# LEDs.net
KiCad netlist of a schematic drawn in Altium Designer
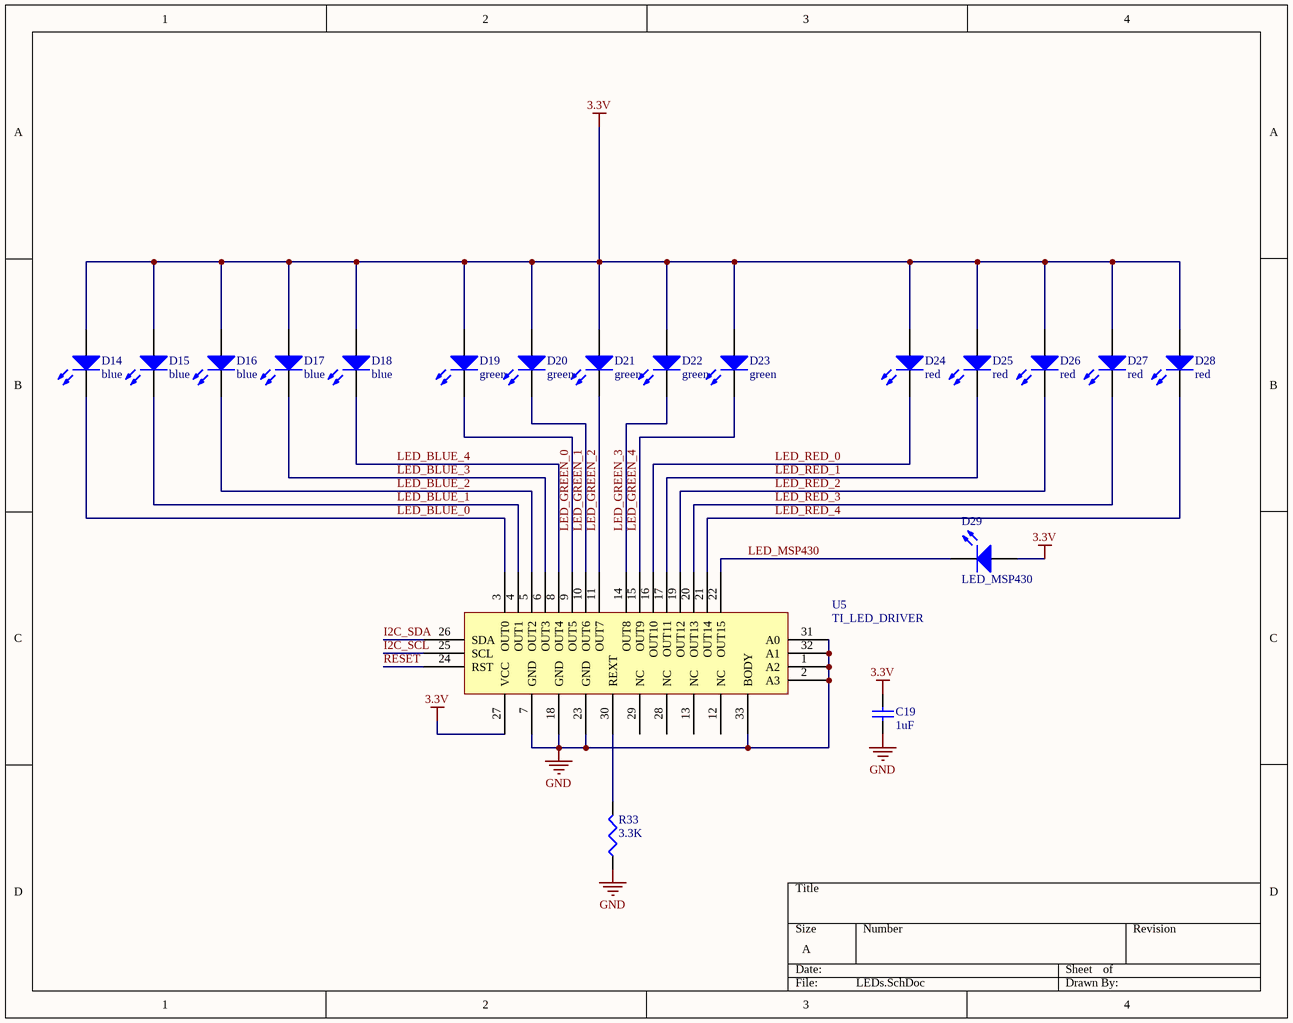
[diagram p0: LEDs.SchDoc]

(export (version "E")
  (design (tool "Eeschema 10.0.6"))
  (components
    (comp (ref "C19")
      (value "1uF")
      (footprint "CAPC1608L")
      (description "Capacitor (Semiconductor SIM Model)")
      (fields (field (name "Comment") "Cap Semi") (field (name "PUBLISHER") "Altium Limited"))
      (libsource (lib "Miscellaneous Devices") (part "Cap Semi"))
    )
    (comp (ref "D14") (value "blue") (footprint "SurfaceMount(603)") (libsource (lib "mrone") (part "LED")))
    (comp (ref "D15") (value "blue") (footprint "SurfaceMount(603)") (libsource (lib "mrone") (part "LED")))
    (comp (ref "D16") (value "blue") (footprint "SurfaceMount(603)") (libsource (lib "mrone") (part "LED")))
    (comp (ref "D17") (value "blue") (footprint "SurfaceMount(603)") (libsource (lib "mrone") (part "LED")))
    (comp (ref "D18") (value "blue") (footprint "SurfaceMount(603)") (libsource (lib "mrone") (part "LED")))
    (comp (ref "D19") (value "green") (footprint "SurfaceMount(603)") (libsource (lib "mrone") (part "LED")))
    (comp (ref "D20") (value "green") (footprint "SurfaceMount(603)") (libsource (lib "mrone") (part "LED")))
    (comp (ref "D21") (value "green") (footprint "SurfaceMount(603)") (libsource (lib "mrone") (part "LED")))
    (comp (ref "D22") (value "green") (footprint "SurfaceMount(603)") (libsource (lib "mrone") (part "LED")))
    (comp (ref "D23") (value "green") (footprint "SurfaceMount(603)") (libsource (lib "mrone") (part "LED")))
    (comp (ref "D24") (value "red") (footprint "SurfaceMount(603)") (libsource (lib "mrone") (part "LED")))
    (comp (ref "D25") (value "red") (footprint "SurfaceMount(603)") (libsource (lib "mrone") (part "LED")))
    (comp (ref "D26") (value "red") (footprint "SurfaceMount(603)") (libsource (lib "mrone") (part "LED")))
    (comp (ref "D27") (value "red") (footprint "SurfaceMount(603)") (libsource (lib "mrone") (part "LED")))
    (comp (ref "D28") (value "red") (footprint "SurfaceMount(603)") (libsource (lib "mrone") (part "LED")))
    (comp (ref "D29")
      (value "LED_MSP430")
      (footprint "SurfaceMount(603)")
      (libsource (lib "") (part "LED_1"))
    )
    (comp (ref "R33")
      (value "3.3K")
      (footprint "RESC1608L")
      (description "Resistor")
      (fields (field (name "Comment") "Res3") (field (name "PUBLISHER") "Altium Limited"))
      (libsource (lib "Miscellaneous Devices") (part "Res3"))
    )
    (comp (ref "U5")
      (value "TI_LED_DRIVER")
      (footprint "QFN32-LEDTLC59116")
      (libsource (lib "mrone") (part "TLC59116LEDDRIVER"))
    )
  )
  (nets
    (net (code "1") (name "/I2C_SCL") (class "Default")
      (node (ref "U5") (pin "25") (pinfunction "SCL_25") (pintype "passive"))
    )
    (net (code "2") (name "/I2C_SDA") (class "Default")
      (node (ref "U5") (pin "26") (pinfunction "SDA_26") (pintype "passive"))
    )
    (net (code "3") (name "/LED_BLUE_0") (class "Default")
      (node (ref "D14") (pin "2") (pinfunction "K_2") (pintype "passive"))
      (node (ref "U5") (pin "3") (pinfunction "OUT0_3") (pintype "passive"))
    )
    (net (code "4") (name "/LED_BLUE_1") (class "Default")
      (node (ref "D15") (pin "2") (pinfunction "K_2") (pintype "passive"))
      (node (ref "U5") (pin "4") (pinfunction "OUT1_4") (pintype "passive"))
    )
    (net (code "5") (name "/LED_BLUE_2") (class "Default")
      (node (ref "D16") (pin "2") (pinfunction "K_2") (pintype "passive"))
      (node (ref "U5") (pin "5") (pinfunction "OUT2_5") (pintype "passive"))
    )
    (net (code "6") (name "/LED_BLUE_3") (class "Default")
      (node (ref "D17") (pin "2") (pinfunction "K_2") (pintype "passive"))
      (node (ref "U5") (pin "6") (pinfunction "OUT3_6") (pintype "passive"))
    )
    (net (code "7") (name "/LED_BLUE_4") (class "Default")
      (node (ref "D18") (pin "2") (pinfunction "K_2") (pintype "passive"))
      (node (ref "U5") (pin "8") (pinfunction "OUT4_8") (pintype "passive"))
    )
    (net (code "8") (name "/LED_GREEN_0") (class "Default")
      (node (ref "D19") (pin "2") (pinfunction "K_2") (pintype "passive"))
      (node (ref "U5") (pin "9") (pinfunction "OUT5_9") (pintype "passive"))
    )
    (net (code "9") (name "/LED_GREEN_1") (class "Default")
      (node (ref "D20") (pin "2") (pinfunction "K_2") (pintype "passive"))
      (node (ref "U5") (pin "10") (pinfunction "OUT6_10") (pintype "passive"))
    )
    (net (code "10") (name "/LED_GREEN_2") (class "Default")
      (node (ref "D21") (pin "2") (pinfunction "K_2") (pintype "passive"))
      (node (ref "U5") (pin "11") (pinfunction "OUT7_11") (pintype "passive"))
    )
    (net (code "11") (name "/LED_GREEN_3") (class "Default")
      (node (ref "D22") (pin "2") (pinfunction "K_2") (pintype "passive"))
      (node (ref "U5") (pin "14") (pinfunction "OUT8_14") (pintype "passive"))
    )
    (net (code "12") (name "/LED_GREEN_4") (class "Default")
      (node (ref "D23") (pin "2") (pinfunction "K_2") (pintype "passive"))
      (node (ref "U5") (pin "15") (pinfunction "OUT9_15") (pintype "passive"))
    )
    (net (code "13") (name "/LED_MSP430") (class "Default")
      (node (ref "D29") (pin "2") (pinfunction "K_2") (pintype "passive"))
      (node (ref "U5") (pin "22") (pinfunction "OUT15_22") (pintype "passive"))
    )
    (net (code "14") (name "/LED_RED_0") (class "Default")
      (node (ref "D24") (pin "2") (pinfunction "K_2") (pintype "passive"))
      (node (ref "U5") (pin "16") (pinfunction "OUT10_16") (pintype "passive"))
    )
    (net (code "15") (name "/LED_RED_1") (class "Default")
      (node (ref "D25") (pin "2") (pinfunction "K_2") (pintype "passive"))
      (node (ref "U5") (pin "17") (pinfunction "OUT11_17") (pintype "passive"))
    )
    (net (code "16") (name "/LED_RED_2") (class "Default")
      (node (ref "D26") (pin "2") (pinfunction "K_2") (pintype "passive"))
      (node (ref "U5") (pin "19") (pinfunction "OUT12_19") (pintype "passive"))
    )
    (net (code "17") (name "/LED_RED_3") (class "Default")
      (node (ref "D27") (pin "2") (pinfunction "K_2") (pintype "passive"))
      (node (ref "U5") (pin "20") (pinfunction "OUT13_20") (pintype "passive"))
    )
    (net (code "18") (name "/LED_RED_4") (class "Default")
      (node (ref "D28") (pin "2") (pinfunction "K_2") (pintype "passive"))
      (node (ref "U5") (pin "21") (pinfunction "OUT14_21") (pintype "passive"))
    )
    (net (code "19") (name "/RESET") (class "Default")
      (node (ref "U5") (pin "24") (pinfunction "RST_24") (pintype "passive"))
    )
    (net (code "20") (name "3.3V") (class "Default")
      (node (ref "C19") (pin "2") (pinfunction "2_2") (pintype "passive"))
      (node (ref "D14") (pin "1") (pinfunction "A_1") (pintype "passive"))
      (node (ref "D15") (pin "1") (pinfunction "A_1") (pintype "passive"))
      (node (ref "D16") (pin "1") (pinfunction "A_1") (pintype "passive"))
      (node (ref "D17") (pin "1") (pinfunction "A_1") (pintype "passive"))
      (node (ref "D18") (pin "1") (pinfunction "A_1") (pintype "passive"))
      (node (ref "D19") (pin "1") (pinfunction "A_1") (pintype "passive"))
      (node (ref "D20") (pin "1") (pinfunction "A_1") (pintype "passive"))
      (node (ref "D21") (pin "1") (pinfunction "A_1") (pintype "passive"))
      (node (ref "D22") (pin "1") (pinfunction "A_1") (pintype "passive"))
      (node (ref "D23") (pin "1") (pinfunction "A_1") (pintype "passive"))
      (node (ref "D24") (pin "1") (pinfunction "A_1") (pintype "passive"))
      (node (ref "D25") (pin "1") (pinfunction "A_1") (pintype "passive"))
      (node (ref "D26") (pin "1") (pinfunction "A_1") (pintype "passive"))
      (node (ref "D27") (pin "1") (pinfunction "A_1") (pintype "passive"))
      (node (ref "D28") (pin "1") (pinfunction "A_1") (pintype "passive"))
      (node (ref "D29") (pin "1") (pinfunction "A_1") (pintype "passive"))
      (node (ref "U5") (pin "27") (pinfunction "VCC_27") (pintype "passive"))
    )
    (net (code "21") (name "GND") (class "Default")
      (node (ref "C19") (pin "1") (pinfunction "1_1") (pintype "passive"))
      (node (ref "R33") (pin "1") (pinfunction "1_1") (pintype "passive"))
      (node (ref "U5") (pin "1") (pinfunction "A2_1") (pintype "passive"))
      (node (ref "U5") (pin "18") (pinfunction "GND_18") (pintype "passive"))
      (node (ref "U5") (pin "2") (pinfunction "A3_2") (pintype "passive"))
      (node (ref "U5") (pin "23") (pinfunction "GND_23") (pintype "passive"))
      (node (ref "U5") (pin "31") (pinfunction "A0_31") (pintype "passive"))
      (node (ref "U5") (pin "32") (pinfunction "A1_32") (pintype "passive"))
      (node (ref "U5") (pin "33") (pinfunction "BODY_33") (pintype "passive"))
      (node (ref "U5") (pin "7") (pinfunction "GND_7") (pintype "passive"))
    )
    (net (code "22") (name "Net-(U5-REXT)") (class "Default")
      (node (ref "R33") (pin "2") (pinfunction "2_2") (pintype "passive"))
      (node (ref "U5") (pin "30") (pinfunction "REXT_30") (pintype "passive"))
    )
    (net (code "23") (name "unconnected-(U5-NC-Pad12)") (class "Default")
      (node (ref "U5") (pin "12") (pinfunction "NC_12") (pintype "passive"))
    )
    (net (code "24") (name "unconnected-(U5-NC-Pad13)") (class "Default")
      (node (ref "U5") (pin "13") (pinfunction "NC_13") (pintype "passive"))
    )
    (net (code "25") (name "unconnected-(U5-NC-Pad28)") (class "Default")
      (node (ref "U5") (pin "28") (pinfunction "NC_28") (pintype "passive"))
    )
    (net (code "26") (name "unconnected-(U5-NC-Pad29)") (class "Default")
      (node (ref "U5") (pin "29") (pinfunction "NC_29") (pintype "passive"))
    )
  )
)
